# Radio_module.net
KiCad netlist of a schematic drawn in Altium Designer
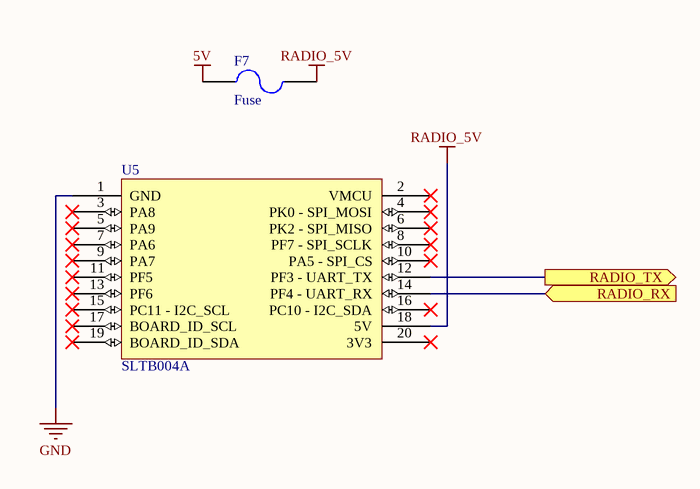
[diagram p0: Radio_module.SchDoc]

(export (version "E")
  (design (tool "Eeschema 10.0.6"))
  (components
    (comp (ref "F7")
      (value "Fuse")
      (footprint "F_0603")
      (fields (field (name "PART NUMBER") "MC06CF.500") (field (name "NI PART NUMBER") "766324-01"))
      (libsource (lib "Components") (part "Fuse"))
    )
    (comp (ref "U5")
      (value "SLTB004A")
      (footprint "SLTB004A")
      (description "SiLabs Thunderboard Sense 2 module")
      (libsource (lib "hallglib") (part "SLTB004A"))
    )
  )
  (nets
    (net (code "1") (name "/RADIO_RX") (class "Default")
      (node (ref "U5") (pin "14") (pinfunction "PF4_-_UART_RX_14") (pintype "bidirectional"))
    )
    (net (code "2") (name "/RADIO_TX") (class "Default")
      (node (ref "U5") (pin "12") (pinfunction "PF3_-_UART_TX_12") (pintype "bidirectional"))
    )
    (net (code "3") (name "5V") (class "Default")
      (node (ref "F7") (pin "1") (pinfunction "1_1") (pintype "passive"))
    )
    (net (code "4") (name "GND") (class "Default")
      (node (ref "U5") (pin "1") (pinfunction "GND_1") (pintype "power_in"))
    )
    (net (code "5") (name "RADIO_5V") (class "Default")
      (node (ref "F7") (pin "2") (pinfunction "2_2") (pintype "passive"))
      (node (ref "U5") (pin "18") (pinfunction "5V_18") (pintype "power_in"))
    )
    (net (code "6") (name "unconnected-(U5-3V3-Pad20)") (class "Default")
      (node (ref "U5") (pin "20") (pinfunction "3V3_20") (pintype "power_in+no_connect"))
    )
    (net (code "7") (name "unconnected-(U5-BOARD_ID_SCL-Pad17)") (class "Default")
      (node (ref "U5") (pin "17") (pinfunction "BOARD_ID_SCL_17") (pintype "bidirectional+no_connect"))
    )
    (net (code "8") (name "unconnected-(U5-BOARD_ID_SDA-Pad19)") (class "Default")
      (node (ref "U5") (pin "19") (pinfunction "BOARD_ID_SDA_19") (pintype "bidirectional+no_connect"))
    )
    (net (code "9") (name "unconnected-(U5-PA5_-_SPI_CS-Pad10)") (class "Default")
      (node (ref "U5") (pin "10") (pinfunction "PA5_-_SPI_CS_10") (pintype "bidirectional+no_connect"))
    )
    (net (code "10") (name "unconnected-(U5-PA6-Pad7)") (class "Default")
      (node (ref "U5") (pin "7") (pinfunction "PA6_7") (pintype "bidirectional+no_connect"))
    )
    (net (code "11") (name "unconnected-(U5-PA7-Pad9)") (class "Default")
      (node (ref "U5") (pin "9") (pinfunction "PA7_9") (pintype "bidirectional+no_connect"))
    )
    (net (code "12") (name "unconnected-(U5-PA8-Pad3)") (class "Default")
      (node (ref "U5") (pin "3") (pinfunction "PA8_3") (pintype "bidirectional+no_connect"))
    )
    (net (code "13") (name "unconnected-(U5-PA9-Pad5)") (class "Default")
      (node (ref "U5") (pin "5") (pinfunction "PA9_5") (pintype "bidirectional+no_connect"))
    )
    (net (code "14") (name "unconnected-(U5-PC10_-_I2C_SDA-Pad16)") (class "Default")
      (node (ref "U5") (pin "16") (pinfunction "PC10_-_I2C_SDA_16") (pintype "bidirectional+no_connect"))
    )
    (net (code "15") (name "unconnected-(U5-PC11_-_I2C_SCL-Pad15)") (class "Default")
      (node (ref "U5") (pin "15") (pinfunction "PC11_-_I2C_SCL_15") (pintype "bidirectional+no_connect"))
    )
    (net (code "16") (name "unconnected-(U5-PF5-Pad11)") (class "Default")
      (node (ref "U5") (pin "11") (pinfunction "PF5_11") (pintype "bidirectional+no_connect"))
    )
    (net (code "17") (name "unconnected-(U5-PF6-Pad13)") (class "Default")
      (node (ref "U5") (pin "13") (pinfunction "PF6_13") (pintype "bidirectional+no_connect"))
    )
    (net (code "18") (name "unconnected-(U5-PF7_-_SPI_SCLK-Pad8)") (class "Default")
      (node (ref "U5") (pin "8") (pinfunction "PF7_-_SPI_SCLK_8") (pintype "bidirectional+no_connect"))
    )
    (net (code "19") (name "unconnected-(U5-PK0_-_SPI_MOSI-Pad4)") (class "Default")
      (node (ref "U5") (pin "4") (pinfunction "PK0_-_SPI_MOSI_4") (pintype "bidirectional+no_connect"))
    )
    (net (code "20") (name "unconnected-(U5-PK2_-_SPI_MISO-Pad6)") (class "Default")
      (node (ref "U5") (pin "6") (pinfunction "PK2_-_SPI_MISO_6") (pintype "bidirectional+no_connect"))
    )
    (net (code "21") (name "unconnected-(U5-VMCU-Pad2)") (class "Default")
      (node (ref "U5") (pin "2") (pinfunction "VMCU_2") (pintype "power_in+no_connect"))
    )
  )
)
